# garden_raspberry.net
KiCad netlist of a schematic drawn in EAGLE
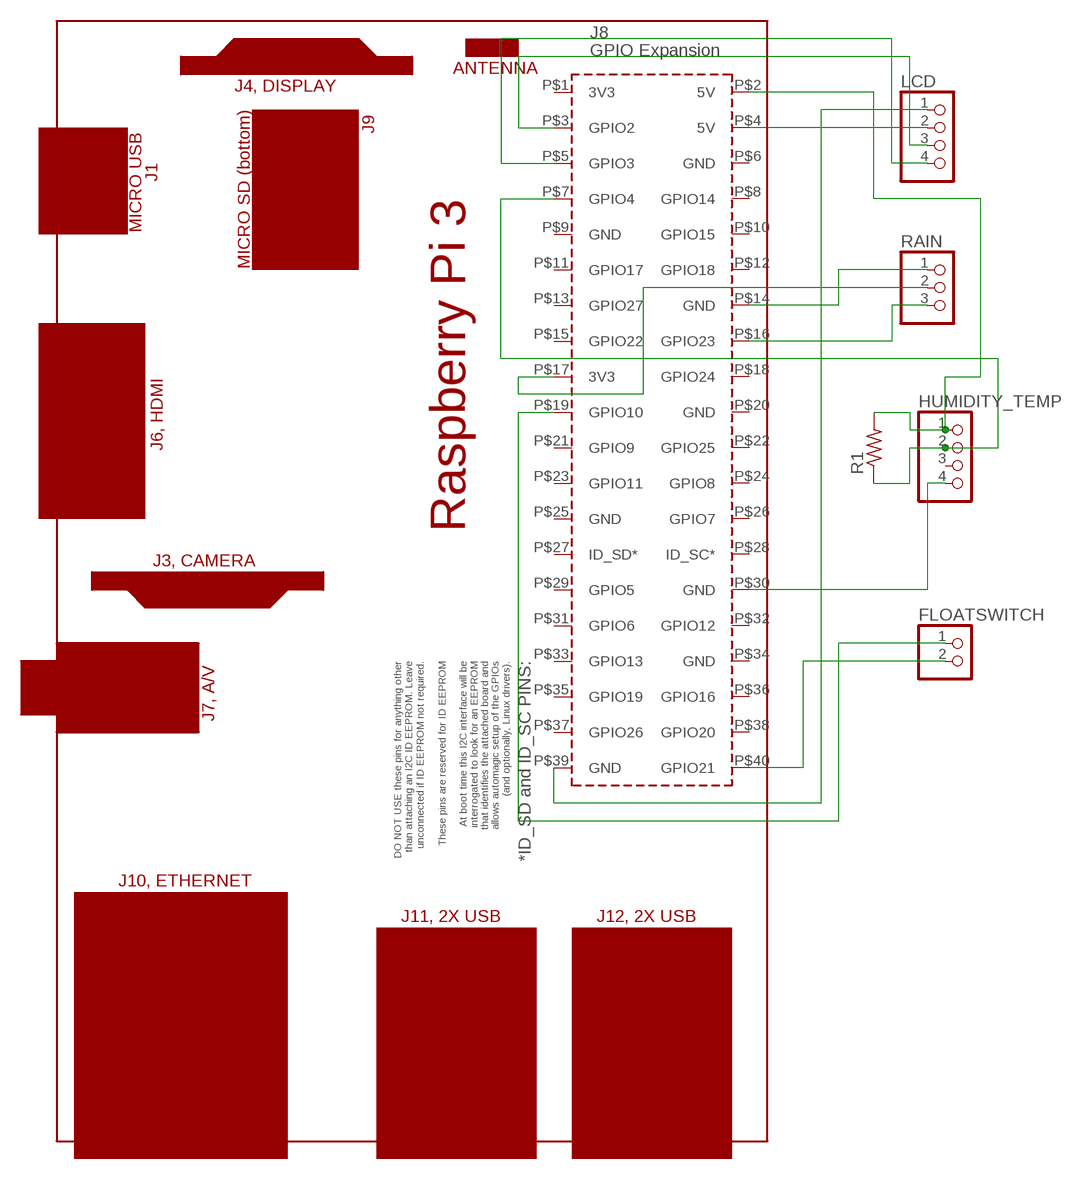
[diagram p0: schematic, sheet 1]

(export (version "E")
  (design (tool "Eeschema 10.0.6"))
  (components
    (comp (ref "FLOATSWITCH")
      (value "PINHD-1X2")
      (footprint "eagle-import:1X02")
      (libsource (lib "eagle-import") (part "PINHD-1X2"))
    )
    (comp (ref "HUMIDITY_TEMP")
      (value "PINHD-1X4")
      (footprint "eagle-import:1X04")
      (libsource (lib "eagle-import") (part "PINHD-1X4"))
    )
    (comp (ref "LCD")
      (value "PINHD-1X4")
      (footprint "eagle-import:1X04")
      (libsource (lib "eagle-import") (part "PINHD-1X4"))
    )
    (comp (ref "PCB1")
      (value "RPI3RPI3")
      (footprint "eagle-import:RPI3")
      (libsource (lib "eagle-import") (part "RPI3RPI3"))
    )
    (comp (ref "R1")
      (value "R-US_0204/7")
      (footprint "eagle-import:0204_7")
      (libsource (lib "eagle-import") (part "R-US_0204/7"))
    )
    (comp (ref "RAIN")
      (value "PINHD-1X3")
      (footprint "eagle-import:1X03")
      (libsource (lib "eagle-import") (part "PINHD-1X3"))
    )
  )
  (nets
    (net (code "1") (name "Net-(HUMIDITY_TEMP-Pad1)") (class "Default")
      (node (ref "HUMIDITY_TEMP") (pin "1") (pinfunction "1_1") (pintype "passive"))
      (node (ref "PCB1") (pin "P$2") (pinfunction "5V_P$2") (pintype "bidirectional"))
      (node (ref "R1") (pin "2") (pinfunction "2_2") (pintype "passive"))
    )
    (net (code "2") (name "Net-(HUMIDITY_TEMP-Pad4)") (class "Default")
      (node (ref "HUMIDITY_TEMP") (pin "4") (pinfunction "4_4") (pintype "passive"))
      (node (ref "PCB1") (pin "P$30") (pinfunction "GND_P$30") (pintype "bidirectional"))
    )
    (net (code "3") (name "Net-(LCD-Pad1)") (class "Default")
      (node (ref "LCD") (pin "1") (pinfunction "1_1") (pintype "passive"))
      (node (ref "PCB1") (pin "P$39") (pinfunction "GND_P$39") (pintype "bidirectional"))
    )
    (net (code "4") (name "Net-(LCD-Pad2)") (class "Default")
      (node (ref "LCD") (pin "2") (pinfunction "2_2") (pintype "passive"))
      (node (ref "PCB1") (pin "P$4") (pinfunction "5V_P$4") (pintype "bidirectional"))
    )
    (net (code "5") (name "Net-(PCB1-3V3-PadP$17)") (class "Default")
      (node (ref "PCB1") (pin "P$17") (pinfunction "3V3_P$17") (pintype "bidirectional"))
      (node (ref "RAIN") (pin "2") (pinfunction "2_2") (pintype "passive"))
    )
    (net (code "6") (name "Net-(PCB1-GND-PadP$14)") (class "Default")
      (node (ref "PCB1") (pin "P$14") (pinfunction "GND_P$14") (pintype "bidirectional"))
      (node (ref "RAIN") (pin "1") (pinfunction "1_1") (pintype "passive"))
    )
    (net (code "7") (name "Net-(PCB1-GPIO2)") (class "Default")
      (node (ref "LCD") (pin "3") (pinfunction "3_3") (pintype "passive"))
      (node (ref "PCB1") (pin "P$3") (pinfunction "GPIO2_P$3") (pintype "bidirectional"))
    )
    (net (code "8") (name "Net-(PCB1-GPIO3)") (class "Default")
      (node (ref "LCD") (pin "4") (pinfunction "4_4") (pintype "passive"))
      (node (ref "PCB1") (pin "P$5") (pinfunction "GPIO3_P$5") (pintype "bidirectional"))
    )
    (net (code "9") (name "Net-(PCB1-GPIO4)") (class "Default")
      (node (ref "HUMIDITY_TEMP") (pin "2") (pinfunction "2_2") (pintype "passive"))
      (node (ref "PCB1") (pin "P$7") (pinfunction "GPIO4_P$7") (pintype "bidirectional"))
      (node (ref "R1") (pin "1") (pinfunction "1_1") (pintype "passive"))
    )
    (net (code "10") (name "Net-(PCB1-GPIO10)") (class "Default")
      (node (ref "FLOATSWITCH") (pin "1") (pinfunction "1_1") (pintype "passive"))
      (node (ref "PCB1") (pin "P$19") (pinfunction "GPIO10_P$19") (pintype "bidirectional"))
    )
    (net (code "11") (name "Net-(PCB1-GPIO21)") (class "Default")
      (node (ref "FLOATSWITCH") (pin "2") (pinfunction "2_2") (pintype "passive"))
      (node (ref "PCB1") (pin "P$40") (pinfunction "GPIO21_P$40") (pintype "bidirectional"))
    )
    (net (code "12") (name "Net-(PCB1-GPIO23)") (class "Default")
      (node (ref "PCB1") (pin "P$16") (pinfunction "GPIO23_P$16") (pintype "bidirectional"))
      (node (ref "RAIN") (pin "3") (pinfunction "3_3") (pintype "passive"))
    )
    (net (code "13") (name "unconnected-(HUMIDITY_TEMP-Pad3)") (class "Default")
      (node (ref "HUMIDITY_TEMP") (pin "3") (pinfunction "3_3") (pintype "passive"))
    )
    (net (code "14") (name "unconnected-(PCB1-3V3-PadP$1)") (class "Default")
      (node (ref "PCB1") (pin "P$1") (pinfunction "3V3_P$1") (pintype "bidirectional"))
    )
    (net (code "15") (name "unconnected-(PCB1-GND-PadP$6)") (class "Default")
      (node (ref "PCB1") (pin "P$6") (pinfunction "GND_P$6") (pintype "bidirectional"))
    )
    (net (code "16") (name "unconnected-(PCB1-GND-PadP$9)") (class "Default")
      (node (ref "PCB1") (pin "P$9") (pinfunction "GND_P$9") (pintype "bidirectional"))
    )
    (net (code "17") (name "unconnected-(PCB1-GND-PadP$20)") (class "Default")
      (node (ref "PCB1") (pin "P$20") (pinfunction "GND_P$20") (pintype "bidirectional"))
    )
    (net (code "18") (name "unconnected-(PCB1-GND-PadP$25)") (class "Default")
      (node (ref "PCB1") (pin "P$25") (pinfunction "GND_P$25") (pintype "bidirectional"))
    )
    (net (code "19") (name "unconnected-(PCB1-GND-PadP$34)") (class "Default")
      (node (ref "PCB1") (pin "P$34") (pinfunction "GND_P$34") (pintype "bidirectional"))
    )
    (net (code "20") (name "unconnected-(PCB1-GPIO5-PadP$29)") (class "Default")
      (node (ref "PCB1") (pin "P$29") (pinfunction "GPIO5_P$29") (pintype "bidirectional"))
    )
    (net (code "21") (name "unconnected-(PCB1-GPIO6-PadP$31)") (class "Default")
      (node (ref "PCB1") (pin "P$31") (pinfunction "GPIO6_P$31") (pintype "bidirectional"))
    )
    (net (code "22") (name "unconnected-(PCB1-GPIO7-PadP$26)") (class "Default")
      (node (ref "PCB1") (pin "P$26") (pinfunction "GPIO7_P$26") (pintype "bidirectional"))
    )
    (net (code "23") (name "unconnected-(PCB1-GPIO8-PadP$24)") (class "Default")
      (node (ref "PCB1") (pin "P$24") (pinfunction "GPIO8_P$24") (pintype "bidirectional"))
    )
    (net (code "24") (name "unconnected-(PCB1-GPIO9-PadP$21)") (class "Default")
      (node (ref "PCB1") (pin "P$21") (pinfunction "GPIO9_P$21") (pintype "bidirectional"))
    )
    (net (code "25") (name "unconnected-(PCB1-GPIO11-PadP$23)") (class "Default")
      (node (ref "PCB1") (pin "P$23") (pinfunction "GPIO11_P$23") (pintype "bidirectional"))
    )
    (net (code "26") (name "unconnected-(PCB1-GPIO12-PadP$32)") (class "Default")
      (node (ref "PCB1") (pin "P$32") (pinfunction "GPIO12_P$32") (pintype "bidirectional"))
    )
    (net (code "27") (name "unconnected-(PCB1-GPIO13-PadP$33)") (class "Default")
      (node (ref "PCB1") (pin "P$33") (pinfunction "GPIO13_P$33") (pintype "bidirectional"))
    )
    (net (code "28") (name "unconnected-(PCB1-GPIO14-PadP$8)") (class "Default")
      (node (ref "PCB1") (pin "P$8") (pinfunction "GPIO14_P$8") (pintype "bidirectional"))
    )
    (net (code "29") (name "unconnected-(PCB1-GPIO15-PadP$10)") (class "Default")
      (node (ref "PCB1") (pin "P$10") (pinfunction "GPIO15_P$10") (pintype "bidirectional"))
    )
    (net (code "30") (name "unconnected-(PCB1-GPIO16-PadP$36)") (class "Default")
      (node (ref "PCB1") (pin "P$36") (pinfunction "GPIO16_P$36") (pintype "bidirectional"))
    )
    (net (code "31") (name "unconnected-(PCB1-GPIO17-PadP$11)") (class "Default")
      (node (ref "PCB1") (pin "P$11") (pinfunction "GPIO17_P$11") (pintype "bidirectional"))
    )
    (net (code "32") (name "unconnected-(PCB1-GPIO18-PadP$12)") (class "Default")
      (node (ref "PCB1") (pin "P$12") (pinfunction "GPIO18_P$12") (pintype "bidirectional"))
    )
    (net (code "33") (name "unconnected-(PCB1-GPIO19-PadP$35)") (class "Default")
      (node (ref "PCB1") (pin "P$35") (pinfunction "GPIO19_P$35") (pintype "bidirectional"))
    )
    (net (code "34") (name "unconnected-(PCB1-GPIO20-PadP$38)") (class "Default")
      (node (ref "PCB1") (pin "P$38") (pinfunction "GPIO20_P$38") (pintype "bidirectional"))
    )
    (net (code "35") (name "unconnected-(PCB1-GPIO22-PadP$15)") (class "Default")
      (node (ref "PCB1") (pin "P$15") (pinfunction "GPIO22_P$15") (pintype "bidirectional"))
    )
    (net (code "36") (name "unconnected-(PCB1-GPIO24-PadP$18)") (class "Default")
      (node (ref "PCB1") (pin "P$18") (pinfunction "GPIO24_P$18") (pintype "bidirectional"))
    )
    (net (code "37") (name "unconnected-(PCB1-GPIO25-PadP$22)") (class "Default")
      (node (ref "PCB1") (pin "P$22") (pinfunction "GPIO25_P$22") (pintype "bidirectional"))
    )
    (net (code "38") (name "unconnected-(PCB1-GPIO26-PadP$37)") (class "Default")
      (node (ref "PCB1") (pin "P$37") (pinfunction "GPIO26_P$37") (pintype "bidirectional"))
    )
    (net (code "39") (name "unconnected-(PCB1-GPIO27-PadP$13)") (class "Default")
      (node (ref "PCB1") (pin "P$13") (pinfunction "GPIO27_P$13") (pintype "bidirectional"))
    )
    (net (code "40") (name "unconnected-(PCB1-ID_SC*-PadP$28)") (class "Default")
      (node (ref "PCB1") (pin "P$28") (pinfunction "ID_SC*_P$28") (pintype "bidirectional"))
    )
    (net (code "41") (name "unconnected-(PCB1-ID_SD*-PadP$27)") (class "Default")
      (node (ref "PCB1") (pin "P$27") (pinfunction "ID_SD*_P$27") (pintype "bidirectional"))
    )
  )
)
